# 1819D_Emetteur_DCF.net
KiCad netlist of a schematic drawn in Altium Designer
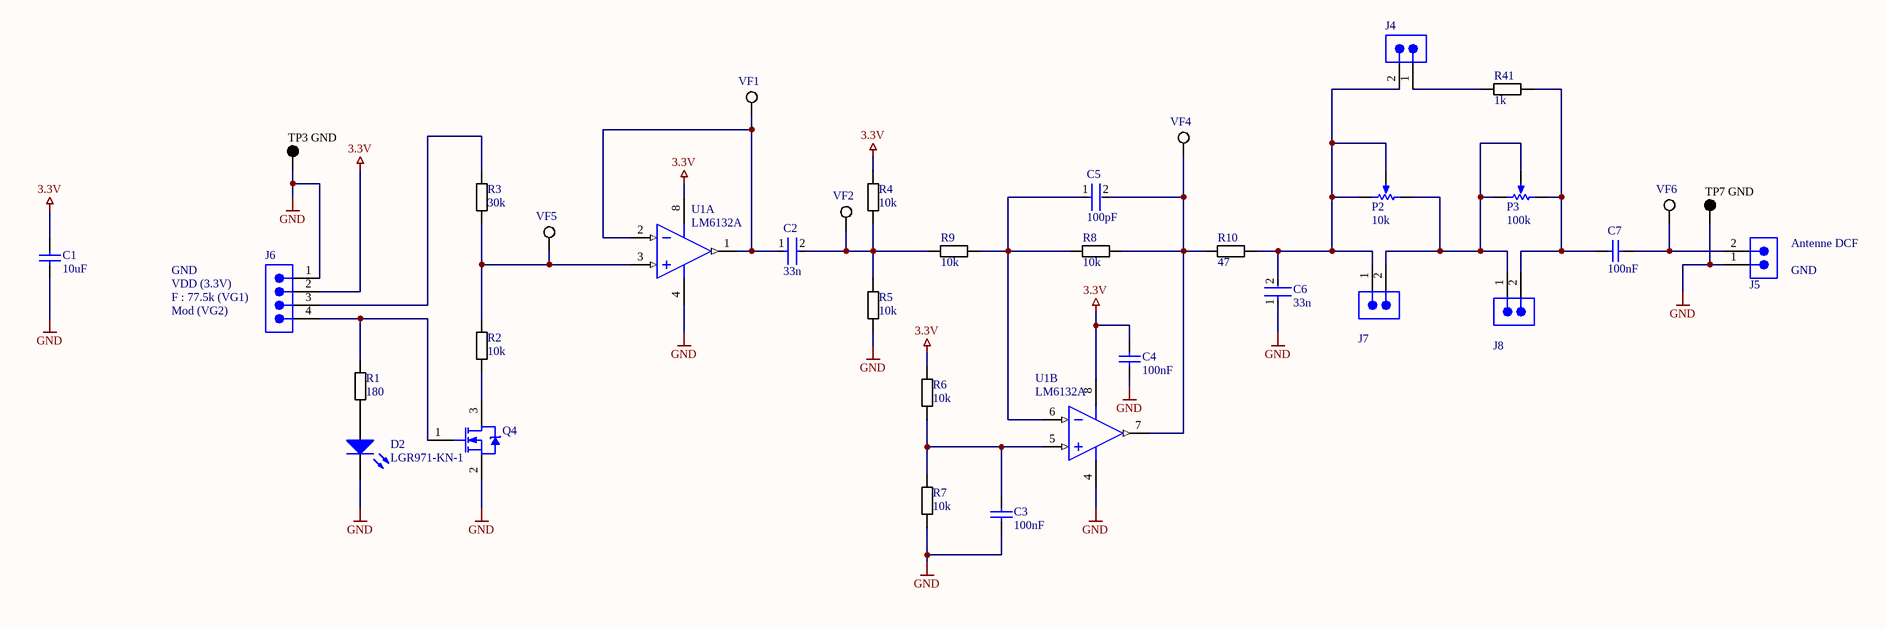
[diagram p0: 1819D_Emetteur_DCF.SchDoc]

(export (version "E")
  (design (tool "Eeschema 10.0.6"))
  (components
    (comp (ref "C1")
      (value "10uF")
      (footprint "CAPC2013X135X45NL10T25")
      (fields (field (name "MANUFACTURER") "Murata") (field (name "PART NUMBER") "GRM21BF51C106ZE15L"))
      (libsource (lib "Altium Content Vault") (part "CAP"))
    )
    (comp (ref "C2")
      (value "33n")
      (footprint "FP-C1206C-EB-IPC_B")
      (description "Multilayer Ceramic Capacitor, C Series, 0.033 - F, - 10%, X7r, 50 V, 1206 [3216 Metric]")
      (fields
        (field (name "MANUFACTURER") "KEMET")
        (field (name "MANUFACTURER PART NUMBER") "C1206C333K5RACTU")
      )
      (libsource (lib "Altium Content Vault") (part "b4654b650e69147ec39a6b967a45e02"))
    )
    (comp (ref "C3")
      (value "100nF")
      (footprint "CAPC2013X140X50LL20T25")
      (fields
        (field (name "PART NUMBER") "08051A470JAT2A")
        (field (name "MANUFACTURER") "AVX Interconnect / Elco")
      )
      (libsource (lib "Altium Content Vault") (part "CAP"))
    )
    (comp (ref "C4")
      (value "100nF")
      (footprint "CAPC2013X140X50LL20T25")
      (fields
        (field (name "PART NUMBER") "08051A470JAT2A")
        (field (name "MANUFACTURER") "AVX Interconnect / Elco")
      )
      (libsource (lib "Altium Content Vault") (part "CAP"))
    )
    (comp (ref "C5")
      (value "100pF")
      (footprint "FP-C0805C-DN-MFG")
      (description "CAP CER 100PF 50V C0G/NP0 0805")
      (fields
        (field (name "OCTOPART") "https://octopart.com/c0805c101j5gactu-kemet-100795")
        (field (name "TOLERANCE") "0.05")
      )
      (libsource (lib "Altium Content Vault") (part "b4654b650e69147ec39a6b967a45e02"))
    )
    (comp (ref "C6")
      (value "33n")
      (footprint "FP-C1206C-EB-IPC_B")
      (description "Multilayer Ceramic Capacitor, C Series, 0.033 - F, - 10%, X7r, 50 V, 1206 [3216 Metric]")
      (fields
        (field (name "MANUFACTURER") "KEMET")
        (field (name "MANUFACTURER PART NUMBER") "C1206C333K5RACTU")
      )
      (libsource (lib "Altium Content Vault") (part "b4654b650e69147ec39a6b967a45e02"))
    )
    (comp (ref "C7")
      (value "100nF")
      (footprint "CAPC2013X140X50LL20T25")
      (fields
        (field (name "PART NUMBER") "08051A470JAT2A")
        (field (name "MANUFACTURER") "AVX Interconnect / Elco")
      )
      (libsource (lib "Altium Content Vault") (part "CAP"))
    )
    (comp (ref "D2")
      (value "LGR971-KN-1")
      (footprint "LED_0805")
      (description "SMD mono-color Chip LED, 0805, Green")
      (fields (field (name "MANUFACTURER") "Wuerth Elektronik"))
      (libsource (lib "Local_Lib") (part "LGR971-KN-1"))
    )
    (comp (ref "J4")
      (value "TSW-102-26-L-S")
      (footprint "SMTC-TSW-102-26-XX-S")
      (description "0.025\" SQ Post Header, Through-hole, Vertical, -55 to 125 degC, 2.54 mm Pitch, 2-Pin, Male, RoHS")
      (fields (field (name "MANUFACTURER") "Samtec"))
      (libsource (lib "Altium Content Vault") (part "SMTC-TSW-102-X-X-S-X"))
    )
    (comp (ref "J5")
      (value "TSW-102-26-L-S")
      (footprint "SMTC-TSW-102-26-XX-S")
      (description "0.025\" SQ Post Header, Through-hole, Vertical, -55 to 125 degC, 2.54 mm Pitch, 2-Pin, Male, RoHS")
      (fields (field (name "MANUFACTURER") "Samtec"))
      (libsource (lib "Altium Content Vault") (part "SMTC-TSW-102-X-X-S-X"))
    )
    (comp (ref "J6")
      (value "TSW-104-08-G-S")
      (footprint "SMTC-TSW-104-08-X-S")
      (description "0.025\" SQ Post Header, Through-hole, Vertical, -55 to 125 degC, 2.54 mm Pitch, 4-Pin, Male, RoHS")
      (fields (field (name "MANUFACTURER") "Samtec"))
      (libsource (lib "Altium Content Vault") (part "SMTC-TSW-104-08-X-S"))
    )
    (comp (ref "J7")
      (value "TSW-102-26-L-S")
      (footprint "SMTC-TSW-102-26-XX-S")
      (description "0.025\" SQ Post Header, Through-hole, Vertical, -55 to 125 degC, 2.54 mm Pitch, 2-Pin, Male, RoHS")
      (fields (field (name "MANUFACTURER") "Samtec"))
      (libsource (lib "Altium Content Vault") (part "SMTC-TSW-102-X-X-S-X"))
    )
    (comp (ref "J8")
      (value "TSW-102-26-L-S")
      (footprint "SMTC-TSW-102-26-XX-S")
      (description "0.025\" SQ Post Header, Through-hole, Vertical, -55 to 125 degC, 2.54 mm Pitch, 2-Pin, Male, RoHS")
      (fields (field (name "MANUFACTURER") "Samtec"))
      (libsource (lib "Altium Content Vault") (part "SMTC-TSW-102-X-X-S-X"))
    )
    (comp (ref "P2")
      (value "10k")
      (footprint "BOUR-3362P")
      (description "Square Trimpot(R) Trimming Potentiometer, 10 KOhm, 300 V, -55 to 125 degC, 3-Pin THD, RoHS, Tube")
      (fields (field (name "TOLERANCE") "1%"))
      (libsource (lib "Altium Content Vault") (part "RES-POT-3"))
    )
    (comp (ref "P3")
      (value "100k")
      (footprint "BOUR-3362P")
      (description "Square Trimpot(R) Trimming Potentiometer, 100 KOhm, 300 V, -55 to 125 degC, 3-Pin THD, RoHS, Tube")
      (fields (field (name "TOLERANCE") "1%"))
      (libsource (lib "Altium Content Vault") (part "RES-POT-3"))
    )
    (comp (ref "Q4")
      (value "IRLML2402TRPBF")
      (footprint "INTR-IRLML2402TRPBF-3_V")
      (description "HEXFET(R) Power MOSFET, N-Channel, 20 V, 1.2 A, 3-Pin SOT-23, RoHS, Tape and Reel")
      (fields (field (name "MANUFACTURER") "International Rectifier"))
      (libsource (lib "Altium Content Vault") (part "NEMOS-GSD-3_A"))
    )
    (comp (ref "R1")
      (value "180")
      (footprint "RESC2013X50X30NL20T20")
      (libsource (lib "LibComposant1819") (part "Resistance"))
    )
    (comp (ref "R2")
      (value "10k")
      (footprint "RESC2013X50X30NL20T20")
      (libsource (lib "LibComposant1819") (part "Resistance"))
    )
    (comp (ref "R3")
      (value "30k")
      (footprint "RESC2013X50X30NL20T20")
      (libsource (lib "LibComposant1819") (part "Resistance"))
    )
    (comp (ref "R4")
      (value "10k")
      (footprint "RESC2013X50X30NL20T20")
      (libsource (lib "LibComposant1819") (part "Resistance"))
    )
    (comp (ref "R5")
      (value "10k")
      (footprint "RESC2013X50X30NL20T20")
      (libsource (lib "LibComposant1819") (part "Resistance"))
    )
    (comp (ref "R6")
      (value "10k")
      (footprint "RESC2013X50X30NL20T20")
      (libsource (lib "") (part "Resistance_2"))
    )
    (comp (ref "R7")
      (value "10k")
      (footprint "RESC2013X50X30NL20T20")
      (libsource (lib "") (part "Resistance_2"))
    )
    (comp (ref "R8")
      (value "10k")
      (footprint "RESC2013X50X30NL20T20")
      (libsource (lib "") (part "Resistance_1"))
    )
    (comp (ref "R9")
      (value "10k")
      (footprint "RESC2013X50X30NL20T20")
      (libsource (lib "") (part "Resistance_1"))
    )
    (comp (ref "R10")
      (value "47")
      (footprint "RESC2013X50X30NL20T20")
      (libsource (lib "") (part "Resistance_1"))
    )
    (comp (ref "R41")
      (value "1k")
      (footprint "RESC2013X50X30NL20T20")
      (libsource (lib "") (part "Resistance_1"))
    )
    (comp (ref "TP3 GND")
      (value "5011")
      (footprint "KSTN-5011_V")
      (description "Test Point, Black, Through Hole, RoHS, Bulk")
      (fields (field (name "MANUFACTURER") "Keystone"))
      (libsource (lib "Altium Content Vault") (part "TESTPOINT_BLACK"))
    )
    (comp (ref "TP7 GND")
      (value "5011")
      (footprint "KSTN-5011_V")
      (description "Test Point, Black, Through Hole, RoHS, Bulk")
      (fields (field (name "MANUFACTURER") "Keystone"))
      (libsource (lib "Altium Content Vault") (part "TESTPOINT_BLACK"))
    )
    (comp (ref "U1")
      (value "LM6132A")
      (footprint "D0008A_N")
      (description "Dual Low Power 10 MHz Rail-to-Rail I/O Operational Amplifier, 8-pin Narrow SOIC, Pb-Free")
      (fields (field (name "MANUFACTURER") "Texas Instruments"))
      (libsource (lib "Altium Content Vault") (part "AMP-OPA-LM6132-8"))
    )
    (comp (ref "VF1")
      (value "5019")
      (footprint "KSTN-5019_V")
      (description "Test Point, 1 Position SMD, RoHS, Tape and Reel")
      (libsource (lib "Altium Content Vault") (part "TESTPOINT_WHITE"))
    )
    (comp (ref "VF2")
      (value "5019")
      (footprint "KSTN-5019_V")
      (description "Test Point, 1 Position SMD, RoHS, Tape and Reel")
      (libsource (lib "Altium Content Vault") (part "TESTPOINT_WHITE"))
    )
    (comp (ref "VF4")
      (value "5019")
      (footprint "KSTN-5019_V")
      (description "Test Point, 1 Position SMD, RoHS, Tape and Reel")
      (libsource (lib "Altium Content Vault") (part "TESTPOINT_WHITE"))
    )
    (comp (ref "VF5")
      (value "5019")
      (footprint "KSTN-5019_V")
      (description "Test Point, 1 Position SMD, RoHS, Tape and Reel")
      (libsource (lib "Altium Content Vault") (part "TESTPOINT_WHITE"))
    )
    (comp (ref "VF6")
      (value "5019")
      (footprint "KSTN-5019_V")
      (description "Test Point, 1 Position SMD, RoHS, Tape and Reel")
      (libsource (lib "Altium Content Vault") (part "TESTPOINT_WHITE"))
    )
  )
  (nets
    (net (code "1") (name "3.3V") (class "Default")
      (node (ref "C1") (pin "2") (pinfunction "2_2") (pintype "passive"))
      (node (ref "C4") (pin "2") (pinfunction "2_2") (pintype "passive"))
      (node (ref "J6") (pin "2") (pinfunction "2_2") (pintype "passive"))
      (node (ref "R4") (pin "1") (pinfunction "1_1") (pintype "passive"))
      (node (ref "R6") (pin "2") (pinfunction "2_2") (pintype "passive"))
      (node (ref "U1") (pin "8") (pinfunction "V+_8") (pintype "power_in"))
    )
    (net (code "2") (name "GND") (class "Default")
      (node (ref "C1") (pin "1") (pinfunction "1_1") (pintype "passive"))
      (node (ref "C3") (pin "1") (pinfunction "1_1") (pintype "passive"))
      (node (ref "C4") (pin "1") (pinfunction "1_1") (pintype "passive"))
      (node (ref "C6") (pin "1") (pinfunction "1_1") (pintype "passive"))
      (node (ref "D2") (pin "1") (pinfunction "K_1") (pintype "passive"))
      (node (ref "J5") (pin "1") (pinfunction "1_1") (pintype "passive"))
      (node (ref "J6") (pin "1") (pinfunction "1_1") (pintype "passive"))
      (node (ref "Q4") (pin "2") (pinfunction "S_2") (pintype "passive"))
      (node (ref "R5") (pin "2") (pinfunction "2_2") (pintype "passive"))
      (node (ref "R7") (pin "1") (pinfunction "1_1") (pintype "passive"))
      (node (ref "TP3 GND") (pin "1") (pinfunction "1_1") (pintype "passive"))
      (node (ref "TP7 GND") (pin "1") (pinfunction "1_1") (pintype "passive"))
      (node (ref "U1") (pin "4") (pinfunction "V-_4") (pintype "power_in"))
    )
    (net (code "3") (name "Net-(C2-Pad2)") (class "Default")
      (node (ref "C2") (pin "2") (pinfunction "2_2") (pintype "passive"))
      (node (ref "R4") (pin "2") (pinfunction "2_2") (pintype "passive"))
      (node (ref "R5") (pin "1") (pinfunction "1_1") (pintype "passive"))
      (node (ref "R9") (pin "1") (pinfunction "1_1") (pintype "passive"))
      (node (ref "VF2") (pin "1") (pinfunction "1_1") (pintype "passive"))
    )
    (net (code "4") (name "Net-(C7-Pad1)") (class "Default")
      (node (ref "C7") (pin "1") (pinfunction "1_1") (pintype "passive"))
      (node (ref "J5") (pin "2") (pinfunction "2_2") (pintype "passive"))
      (node (ref "VF6") (pin "1") (pinfunction "1_1") (pintype "passive"))
    )
    (net (code "5") (name "Net-(D2-A)") (class "Default")
      (node (ref "D2") (pin "2") (pinfunction "A_2") (pintype "passive"))
      (node (ref "R1") (pin "2") (pinfunction "2_2") (pintype "passive"))
    )
    (net (code "6") (name "Net-(J4-Pad1)") (class "Default")
      (node (ref "J4") (pin "1") (pinfunction "1_1") (pintype "passive"))
      (node (ref "R41") (pin "1") (pinfunction "1_1") (pintype "passive"))
    )
    (net (code "7") (name "Net-(J6-Pad3)") (class "Default")
      (node (ref "J6") (pin "3") (pinfunction "3_3") (pintype "passive"))
      (node (ref "R3") (pin "1") (pinfunction "1_1") (pintype "passive"))
    )
    (net (code "8") (name "Net-(P2-CCW)") (class "Default")
      (node (ref "J7") (pin "2") (pinfunction "2_2") (pintype "passive"))
      (node (ref "J8") (pin "1") (pinfunction "1_1") (pintype "passive"))
      (node (ref "P2") (pin "1") (pinfunction "CCW_1") (pintype "passive"))
      (node (ref "P3") (pin "2") (pinfunction "S_2") (pintype "passive"))
      (node (ref "P3") (pin "3") (pinfunction "CW_3") (pintype "passive"))
    )
    (net (code "9") (name "Net-(P2-CW)") (class "Default")
      (node (ref "C6") (pin "2") (pinfunction "2_2") (pintype "passive"))
      (node (ref "J4") (pin "2") (pinfunction "2_2") (pintype "passive"))
      (node (ref "J7") (pin "1") (pinfunction "1_1") (pintype "passive"))
      (node (ref "P2") (pin "2") (pinfunction "S_2") (pintype "passive"))
      (node (ref "P2") (pin "3") (pinfunction "CW_3") (pintype "passive"))
      (node (ref "R10") (pin "2") (pinfunction "2_2") (pintype "passive"))
    )
    (net (code "10") (name "Net-(P3-CCW)") (class "Default")
      (node (ref "C7") (pin "2") (pinfunction "2_2") (pintype "passive"))
      (node (ref "J8") (pin "2") (pinfunction "2_2") (pintype "passive"))
      (node (ref "P3") (pin "1") (pinfunction "CCW_1") (pintype "passive"))
      (node (ref "R41") (pin "2") (pinfunction "2_2") (pintype "passive"))
    )
    (net (code "11") (name "Net-(Q4-D)") (class "Default")
      (node (ref "Q4") (pin "3") (pinfunction "D_3") (pintype "passive"))
      (node (ref "R2") (pin "2") (pinfunction "2_2") (pintype "passive"))
    )
    (net (code "12") (name "Net-(Q4-G)") (class "Default")
      (node (ref "J6") (pin "4") (pinfunction "4_4") (pintype "passive"))
      (node (ref "Q4") (pin "1") (pinfunction "G_1") (pintype "passive"))
      (node (ref "R1") (pin "1") (pinfunction "1_1") (pintype "passive"))
    )
    (net (code "13") (name "Net-(U1A-INA+)") (class "Default")
      (node (ref "R2") (pin "1") (pinfunction "1_1") (pintype "passive"))
      (node (ref "R3") (pin "2") (pinfunction "2_2") (pintype "passive"))
      (node (ref "U1") (pin "3") (pinfunction "INA+_3") (pintype "input"))
      (node (ref "VF5") (pin "1") (pinfunction "1_1") (pintype "passive"))
    )
    (net (code "14") (name "Net-(U1A-INA-)") (class "Default")
      (node (ref "C2") (pin "1") (pinfunction "1_1") (pintype "passive"))
      (node (ref "U1") (pin "1") (pinfunction "OUTA_1") (pintype "output"))
      (node (ref "U1") (pin "2") (pinfunction "INA-_2") (pintype "input"))
      (node (ref "VF1") (pin "1") (pinfunction "1_1") (pintype "passive"))
    )
    (net (code "15") (name "Net-(U1B-INB+)") (class "Default")
      (node (ref "C3") (pin "2") (pinfunction "2_2") (pintype "passive"))
      (node (ref "R6") (pin "1") (pinfunction "1_1") (pintype "passive"))
      (node (ref "R7") (pin "2") (pinfunction "2_2") (pintype "passive"))
      (node (ref "U1") (pin "5") (pinfunction "INB+_5") (pintype "input"))
    )
    (net (code "16") (name "Net-(U1B-INB-)") (class "Default")
      (node (ref "C5") (pin "1") (pinfunction "1_1") (pintype "passive"))
      (node (ref "R8") (pin "1") (pinfunction "1_1") (pintype "passive"))
      (node (ref "R9") (pin "2") (pinfunction "2_2") (pintype "passive"))
      (node (ref "U1") (pin "6") (pinfunction "INB-_6") (pintype "input"))
    )
    (net (code "17") (name "Net-(U1B-OUTB)") (class "Default")
      (node (ref "C5") (pin "2") (pinfunction "2_2") (pintype "passive"))
      (node (ref "R10") (pin "1") (pinfunction "1_1") (pintype "passive"))
      (node (ref "R8") (pin "2") (pinfunction "2_2") (pintype "passive"))
      (node (ref "U1") (pin "7") (pinfunction "OUTB_7") (pintype "output"))
      (node (ref "VF4") (pin "1") (pinfunction "1_1") (pintype "passive"))
    )
  )
)
